# OMODRI_AbsEnc.net
KiCad netlist of a schematic drawn in Altium Designer
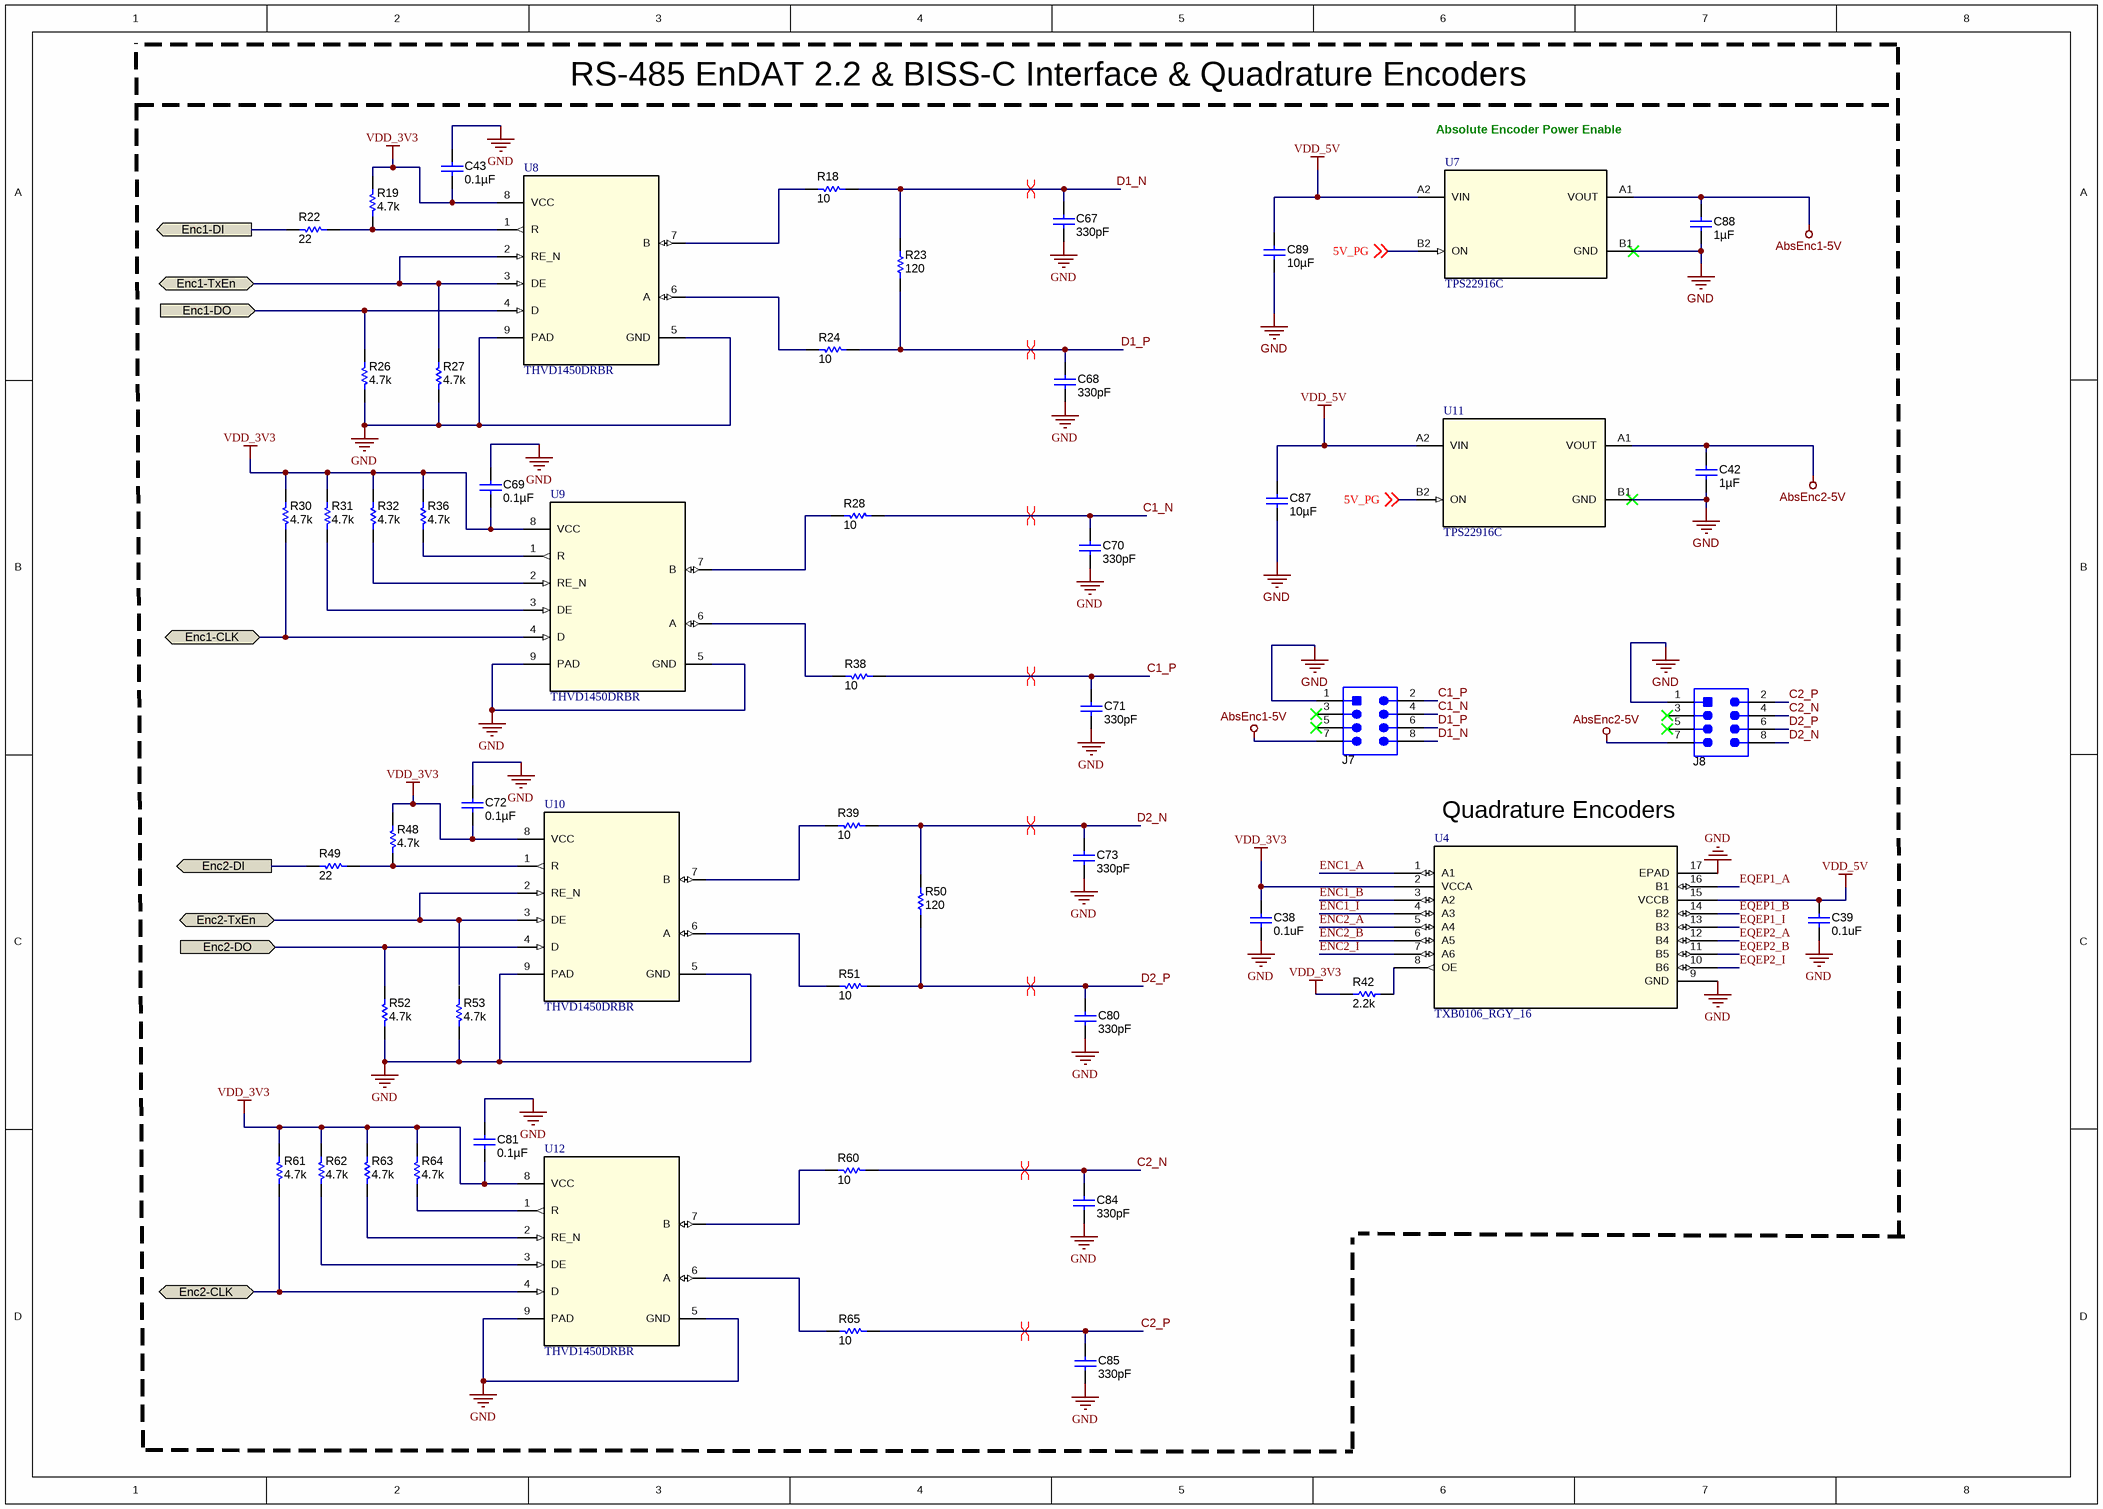
[diagram p0: OMODRI_AbsEnc.SchDoc]

(export (version "E")
  (design (tool "Eeschema 10.0.6"))
  (components
    (comp (ref "C38")
      (value "CL05B104KP5NNNC")
      (footprint "0402")
      (description "CAP, CERM, 0.1 uF, 10 V, +/- 10%, X7R, 0402")
      (fields
        (field (name "VALUEDISPLAYED") "0.1uF")
        (field (name "MANUFACTURER") "Samsung Electro-Mechanics")
        (field (name "PUBLISHER") "Texas Instruments")
      )
      (libsource (lib "Altium Vault - TI") (part "Capacitor"))
    )
    (comp (ref "C39")
      (value "CL05B104KP5NNNC")
      (footprint "0402")
      (description "CAP, CERM, 0.1 uF, 10 V, +/- 10%, X7R, 0402")
      (fields
        (field (name "VALUEDISPLAYED") "0.1uF")
        (field (name "MANUFACTURER") "Samsung Electro-Mechanics")
        (field (name "PUBLISHER") "Texas Instruments")
      )
      (libsource (lib "Altium Vault - TI") (part "Capacitor"))
    )
    (comp (ref "C42")
      (value "TMK212BJ105KG-T")
      (footprint "0805_HV")
      (description "CAP, CERM, 1 µF, 20 V, +/- 10%, X5R, 0805")
      (fields
        (field (name "VALUEDISPLAYED") "1µF")
        (field (name "MANUFACTURER") "Taiyo Yuden")
        (field (name "PUBLISHER") "Texas Instruments")
      )
      (libsource (lib "Capacitor_Ceramic") (part "TMK212BJ105KG-T"))
    )
    (comp (ref "C43")
      (value "06033D104KAT2A")
      (footprint "0603")
      (description "CAP, CERM, 0.1uF, 25V, +/-10%, X5R, 0603")
      (fields
        (field (name "VALUEDISPLAYED") "0.1µF")
        (field (name "MANUFACTURER") "AVX")
        (field (name "PUBLISHER") "Texas Instruments")
      )
      (libsource (lib "Capacitor_Ceramic") (part "06033D104KAT2A"))
    )
    (comp (ref "C67")
      (value "GRM188R71H331KA01D")
      (footprint "0603")
      (description "CAP, CERM, 330pF, 50V, +/-10%, X7R, 0603")
      (fields
        (field (name "VALUEDISPLAYED") "330pF")
        (field (name "MANUFACTURER") "MuRata")
        (field (name "PUBLISHER") "Texas Instruments")
      )
      (libsource (lib "Capacitor_Ceramic") (part "GRM188R71H331KA01D"))
    )
    (comp (ref "C68")
      (value "GRM188R71H331KA01D")
      (footprint "0603")
      (description "CAP, CERM, 330pF, 50V, +/-10%, X7R, 0603")
      (fields
        (field (name "VALUEDISPLAYED") "330pF")
        (field (name "MANUFACTURER") "MuRata")
        (field (name "PUBLISHER") "Texas Instruments")
      )
      (libsource (lib "Capacitor_Ceramic") (part "GRM188R71H331KA01D"))
    )
    (comp (ref "C69")
      (value "06033D104KAT2A")
      (footprint "0603")
      (description "CAP, CERM, 0.1uF, 25V, +/-10%, X5R, 0603")
      (fields
        (field (name "VALUEDISPLAYED") "0.1µF")
        (field (name "MANUFACTURER") "AVX")
        (field (name "PUBLISHER") "Texas Instruments")
      )
      (libsource (lib "Capacitor_Ceramic") (part "06033D104KAT2A"))
    )
    (comp (ref "C70")
      (value "GRM188R71H331KA01D")
      (footprint "0603")
      (description "CAP, CERM, 330pF, 50V, +/-10%, X7R, 0603")
      (fields
        (field (name "VALUEDISPLAYED") "330pF")
        (field (name "MANUFACTURER") "MuRata")
        (field (name "PUBLISHER") "Texas Instruments")
      )
      (libsource (lib "Capacitor_Ceramic") (part "GRM188R71H331KA01D"))
    )
    (comp (ref "C71")
      (value "GRM188R71H331KA01D")
      (footprint "0603")
      (description "CAP, CERM, 330pF, 50V, +/-10%, X7R, 0603")
      (fields
        (field (name "VALUEDISPLAYED") "330pF")
        (field (name "MANUFACTURER") "MuRata")
        (field (name "PUBLISHER") "Texas Instruments")
      )
      (libsource (lib "Capacitor_Ceramic") (part "GRM188R71H331KA01D"))
    )
    (comp (ref "C72")
      (value "06033D104KAT2A")
      (footprint "0603")
      (description "CAP, CERM, 0.1uF, 25V, +/-10%, X5R, 0603")
      (fields
        (field (name "VALUEDISPLAYED") "0.1µF")
        (field (name "MANUFACTURER") "AVX")
        (field (name "PUBLISHER") "Texas Instruments")
      )
      (libsource (lib "Capacitor_Ceramic") (part "06033D104KAT2A"))
    )
    (comp (ref "C73")
      (value "GRM188R71H331KA01D")
      (footprint "0603")
      (description "CAP, CERM, 330pF, 50V, +/-10%, X7R, 0603")
      (fields
        (field (name "VALUEDISPLAYED") "330pF")
        (field (name "MANUFACTURER") "MuRata")
        (field (name "PUBLISHER") "Texas Instruments")
      )
      (libsource (lib "Capacitor_Ceramic") (part "GRM188R71H331KA01D"))
    )
    (comp (ref "C80")
      (value "GRM188R71H331KA01D")
      (footprint "0603")
      (description "CAP, CERM, 330pF, 50V, +/-10%, X7R, 0603")
      (fields
        (field (name "VALUEDISPLAYED") "330pF")
        (field (name "MANUFACTURER") "MuRata")
        (field (name "PUBLISHER") "Texas Instruments")
      )
      (libsource (lib "Capacitor_Ceramic") (part "GRM188R71H331KA01D"))
    )
    (comp (ref "C81")
      (value "06033D104KAT2A")
      (footprint "0603")
      (description "CAP, CERM, 0.1uF, 25V, +/-10%, X5R, 0603")
      (fields
        (field (name "VALUEDISPLAYED") "0.1µF")
        (field (name "MANUFACTURER") "AVX")
        (field (name "PUBLISHER") "Texas Instruments")
      )
      (libsource (lib "Capacitor_Ceramic") (part "06033D104KAT2A"))
    )
    (comp (ref "C84")
      (value "GRM188R71H331KA01D")
      (footprint "0603")
      (description "CAP, CERM, 330pF, 50V, +/-10%, X7R, 0603")
      (fields
        (field (name "VALUEDISPLAYED") "330pF")
        (field (name "MANUFACTURER") "MuRata")
        (field (name "PUBLISHER") "Texas Instruments")
      )
      (libsource (lib "Capacitor_Ceramic") (part "GRM188R71H331KA01D"))
    )
    (comp (ref "C85")
      (value "GRM188R71H331KA01D")
      (footprint "0603")
      (description "CAP, CERM, 330pF, 50V, +/-10%, X7R, 0603")
      (fields
        (field (name "VALUEDISPLAYED") "330pF")
        (field (name "MANUFACTURER") "MuRata")
        (field (name "PUBLISHER") "Texas Instruments")
      )
      (libsource (lib "Capacitor_Ceramic") (part "GRM188R71H331KA01D"))
    )
    (comp (ref "C87")
      (value "GRM21BR61E106KA73L")
      (footprint "0805_HV")
      (description "CAP, CERM, 10 µF, 25 V,+/- 10%, X5R, 0805")
      (fields
        (field (name "VALUEDISPLAYED") "10µF")
        (field (name "MANUFACTURER") "MuRata")
        (field (name "PUBLISHER") "Texas Instruments")
      )
      (libsource (lib "Capacitor_Ceramic") (part "GRM21BR61E106KA73L"))
    )
    (comp (ref "C88")
      (value "TMK212BJ105KG-T")
      (footprint "0805_HV")
      (description "CAP, CERM, 1 µF, 20 V, +/- 10%, X5R, 0805")
      (fields
        (field (name "VALUEDISPLAYED") "1µF")
        (field (name "MANUFACTURER") "Taiyo Yuden")
        (field (name "PUBLISHER") "Texas Instruments")
      )
      (libsource (lib "Capacitor_Ceramic") (part "TMK212BJ105KG-T"))
    )
    (comp (ref "C89")
      (value "GRM21BR61E106KA73L")
      (footprint "0805_HV")
      (description "CAP, CERM, 10 µF, 25 V,+/- 10%, X5R, 0805")
      (fields
        (field (name "VALUEDISPLAYED") "10µF")
        (field (name "MANUFACTURER") "MuRata")
        (field (name "PUBLISHER") "Texas Instruments")
      )
      (libsource (lib "Capacitor_Ceramic") (part "GRM21BR61E106KA73L"))
    )
    (comp (ref "J7")
      (value "70246-0801")
      (footprint "Molex_70246-0801")
      (description "Header(shrouded), 2.54mm, 4x2, Gold, TH")
      (fields
        (field (name "MANUFACTURER") "Molex")
        (field (name "SYMBOLCREATOR") "a0411947")
        (field (name "PUBLISHER") "Texas Instruments")
      )
      (libsource (lib "Connectors_Molex") (part "70246-0801"))
    )
    (comp (ref "J8")
      (value "70246-0801")
      (footprint "Molex_70246-0801")
      (description "Header(shrouded), 2.54mm, 4x2, Gold, TH")
      (fields
        (field (name "MANUFACTURER") "Molex")
        (field (name "SYMBOLCREATOR") "a0411947")
        (field (name "PUBLISHER") "Texas Instruments")
      )
      (libsource (lib "Connectors_Molex") (part "70246-0801"))
    )
    (comp (ref "R18")
      (value "10")
      (footprint "0603")
      (description "RES, 10 ohm, 5%, 0.25W, 0603")
      (fields
        (field (name "PARTNUMBER") "CRCW060310R0JNEAHP")
        (field (name "MANUFACTURER") "Vishay-Dale")
        (field (name "PUBLISHER") "Texas Instruments")
      )
      (libsource (lib "Resistor_0603") (part "CRCW060310R0JNEAHP"))
    )
    (comp (ref "R19")
      (value "4.7k")
      (footprint "0603")
      (description "RES, 4.7k ohm, 5%, 0.1W, 0603")
      (fields
        (field (name "PARTNUMBER") "CRCW06034K70JNEA")
        (field (name "MANUFACTURER") "Vishay-Dale")
        (field (name "PUBLISHER") "Texas Instruments")
      )
      (libsource (lib "Resistor_0603") (part "CRCW06034K70JNEA"))
    )
    (comp (ref "R22")
      (value "22")
      (footprint "0603")
      (description "RES, 22 ohm, 5%, 0.1W, 0603")
      (fields
        (field (name "PARTNUMBER") "CRCW060322R0JNEA")
        (field (name "MANUFACTURER") "Vishay-Dale")
        (field (name "PUBLISHER") "Texas Instruments")
      )
      (libsource (lib "Resistor_0603") (part "CRCW060322R0JNEA"))
    )
    (comp (ref "R23")
      (value "CRCW0603120RJNEA")
      (footprint "0603")
      (description "RES, 120, 5%, 0.1 W, 0603")
      (fields
        (field (name "VALUEDISPLAYED") "120")
        (field (name "MANUFACTURER") "Vishay-Dale")
        (field (name "PUBLISHER") "Texas Instruments")
      )
      (libsource (lib "Resistor_0603") (part "CRCW0603120RJNEA"))
    )
    (comp (ref "R24")
      (value "10")
      (footprint "0603")
      (description "RES, 10 ohm, 5%, 0.25W, 0603")
      (fields
        (field (name "PARTNUMBER") "CRCW060310R0JNEAHP")
        (field (name "MANUFACTURER") "Vishay-Dale")
        (field (name "PUBLISHER") "Texas Instruments")
      )
      (libsource (lib "Resistor_0603") (part "CRCW060310R0JNEAHP"))
    )
    (comp (ref "R26")
      (value "4.7k")
      (footprint "0603")
      (description "RES, 4.7k ohm, 5%, 0.1W, 0603")
      (fields
        (field (name "PARTNUMBER") "CRCW06034K70JNEA")
        (field (name "MANUFACTURER") "Vishay-Dale")
        (field (name "PUBLISHER") "Texas Instruments")
      )
      (libsource (lib "Resistor_0603") (part "CRCW06034K70JNEA"))
    )
    (comp (ref "R27")
      (value "4.7k")
      (footprint "0603")
      (description "RES, 4.7k ohm, 5%, 0.1W, 0603")
      (fields
        (field (name "PARTNUMBER") "CRCW06034K70JNEA")
        (field (name "MANUFACTURER") "Vishay-Dale")
        (field (name "PUBLISHER") "Texas Instruments")
      )
      (libsource (lib "Resistor_0603") (part "CRCW06034K70JNEA"))
    )
    (comp (ref "R28")
      (value "10")
      (footprint "0603")
      (description "RES, 10 ohm, 5%, 0.25W, 0603")
      (fields
        (field (name "PARTNUMBER") "CRCW060310R0JNEAHP")
        (field (name "MANUFACTURER") "Vishay-Dale")
        (field (name "PUBLISHER") "Texas Instruments")
      )
      (libsource (lib "Resistor_0603") (part "CRCW060310R0JNEAHP"))
    )
    (comp (ref "R30")
      (value "4.7k")
      (footprint "0603")
      (description "RES, 4.7k ohm, 5%, 0.1W, 0603")
      (fields
        (field (name "PARTNUMBER") "CRCW06034K70JNEA")
        (field (name "MANUFACTURER") "Vishay-Dale")
        (field (name "PUBLISHER") "Texas Instruments")
      )
      (libsource (lib "Resistor_0603") (part "CRCW06034K70JNEA"))
    )
    (comp (ref "R31")
      (value "4.7k")
      (footprint "0603")
      (description "RES, 4.7k ohm, 5%, 0.1W, 0603")
      (fields
        (field (name "PARTNUMBER") "CRCW06034K70JNEA")
        (field (name "MANUFACTURER") "Vishay-Dale")
        (field (name "PUBLISHER") "Texas Instruments")
      )
      (libsource (lib "Resistor_0603") (part "CRCW06034K70JNEA"))
    )
    (comp (ref "R32")
      (value "4.7k")
      (footprint "0603")
      (description "RES, 4.7k ohm, 5%, 0.1W, 0603")
      (fields
        (field (name "PARTNUMBER") "CRCW06034K70JNEA")
        (field (name "MANUFACTURER") "Vishay-Dale")
        (field (name "PUBLISHER") "Texas Instruments")
      )
      (libsource (lib "Resistor_0603") (part "CRCW06034K70JNEA"))
    )
    (comp (ref "R36")
      (value "4.7k")
      (footprint "0603")
      (description "RES, 4.7k ohm, 5%, 0.1W, 0603")
      (fields
        (field (name "PARTNUMBER") "CRCW06034K70JNEA")
        (field (name "MANUFACTURER") "Vishay-Dale")
        (field (name "PUBLISHER") "Texas Instruments")
      )
      (libsource (lib "Resistor_0603") (part "CRCW06034K70JNEA"))
    )
    (comp (ref "R38")
      (value "10")
      (footprint "0603")
      (description "RES, 10 ohm, 5%, 0.25W, 0603")
      (fields
        (field (name "PARTNUMBER") "CRCW060310R0JNEAHP")
        (field (name "MANUFACTURER") "Vishay-Dale")
        (field (name "PUBLISHER") "Texas Instruments")
      )
      (libsource (lib "Resistor_0603") (part "CRCW060310R0JNEAHP"))
    )
    (comp (ref "R39")
      (value "10")
      (footprint "0603")
      (description "RES, 10 ohm, 5%, 0.25W, 0603")
      (fields
        (field (name "PARTNUMBER") "CRCW060310R0JNEAHP")
        (field (name "MANUFACTURER") "Vishay-Dale")
        (field (name "PUBLISHER") "Texas Instruments")
      )
      (libsource (lib "Resistor_0603") (part "CRCW060310R0JNEAHP"))
    )
    (comp (ref "R42")
      (value "CRCW02012K20JNED")
      (footprint "0201")
      (description "RES, 2.2 k, 5%, 0.05 W, 0201")
      (fields (field (name "MANUFACTURER") "Vishay-Dale") (field (name "VALUEDISPLAYED") "2.2k"))
      (libsource (lib "Altium Vault - TI") (part "Resistor"))
    )
    (comp (ref "R48")
      (value "4.7k")
      (footprint "0603")
      (description "RES, 4.7k ohm, 5%, 0.1W, 0603")
      (fields
        (field (name "PARTNUMBER") "CRCW06034K70JNEA")
        (field (name "MANUFACTURER") "Vishay-Dale")
        (field (name "PUBLISHER") "Texas Instruments")
      )
      (libsource (lib "Resistor_0603") (part "CRCW06034K70JNEA"))
    )
    (comp (ref "R49")
      (value "22")
      (footprint "0603")
      (description "RES, 22 ohm, 5%, 0.1W, 0603")
      (fields
        (field (name "PARTNUMBER") "CRCW060322R0JNEA")
        (field (name "MANUFACTURER") "Vishay-Dale")
        (field (name "PUBLISHER") "Texas Instruments")
      )
      (libsource (lib "Resistor_0603") (part "CRCW060322R0JNEA"))
    )
    (comp (ref "R50")
      (value "CRCW0603120RJNEA")
      (footprint "0603")
      (description "RES, 120, 5%, 0.1 W, 0603")
      (fields
        (field (name "VALUEDISPLAYED") "120")
        (field (name "MANUFACTURER") "Vishay-Dale")
        (field (name "PUBLISHER") "Texas Instruments")
      )
      (libsource (lib "Resistor_0603") (part "CRCW0603120RJNEA"))
    )
    (comp (ref "R51")
      (value "10")
      (footprint "0603")
      (description "RES, 10 ohm, 5%, 0.25W, 0603")
      (fields
        (field (name "PARTNUMBER") "CRCW060310R0JNEAHP")
        (field (name "MANUFACTURER") "Vishay-Dale")
        (field (name "PUBLISHER") "Texas Instruments")
      )
      (libsource (lib "Resistor_0603") (part "CRCW060310R0JNEAHP"))
    )
    (comp (ref "R52")
      (value "4.7k")
      (footprint "0603")
      (description "RES, 4.7k ohm, 5%, 0.1W, 0603")
      (fields
        (field (name "PARTNUMBER") "CRCW06034K70JNEA")
        (field (name "MANUFACTURER") "Vishay-Dale")
        (field (name "PUBLISHER") "Texas Instruments")
      )
      (libsource (lib "Resistor_0603") (part "CRCW06034K70JNEA"))
    )
    (comp (ref "R53")
      (value "4.7k")
      (footprint "0603")
      (description "RES, 4.7k ohm, 5%, 0.1W, 0603")
      (fields
        (field (name "PARTNUMBER") "CRCW06034K70JNEA")
        (field (name "MANUFACTURER") "Vishay-Dale")
        (field (name "PUBLISHER") "Texas Instruments")
      )
      (libsource (lib "Resistor_0603") (part "CRCW06034K70JNEA"))
    )
    (comp (ref "R60")
      (value "10")
      (footprint "0603")
      (description "RES, 10 ohm, 5%, 0.25W, 0603")
      (fields
        (field (name "PARTNUMBER") "CRCW060310R0JNEAHP")
        (field (name "MANUFACTURER") "Vishay-Dale")
        (field (name "PUBLISHER") "Texas Instruments")
      )
      (libsource (lib "Resistor_0603") (part "CRCW060310R0JNEAHP"))
    )
    (comp (ref "R61")
      (value "4.7k")
      (footprint "0603")
      (description "RES, 4.7k ohm, 5%, 0.1W, 0603")
      (fields
        (field (name "PARTNUMBER") "CRCW06034K70JNEA")
        (field (name "MANUFACTURER") "Vishay-Dale")
        (field (name "PUBLISHER") "Texas Instruments")
      )
      (libsource (lib "Resistor_0603") (part "CRCW06034K70JNEA"))
    )
    (comp (ref "R62")
      (value "4.7k")
      (footprint "0603")
      (description "RES, 4.7k ohm, 5%, 0.1W, 0603")
      (fields
        (field (name "PARTNUMBER") "CRCW06034K70JNEA")
        (field (name "MANUFACTURER") "Vishay-Dale")
        (field (name "PUBLISHER") "Texas Instruments")
      )
      (libsource (lib "Resistor_0603") (part "CRCW06034K70JNEA"))
    )
    (comp (ref "R63")
      (value "4.7k")
      (footprint "0603")
      (description "RES, 4.7k ohm, 5%, 0.1W, 0603")
      (fields
        (field (name "PARTNUMBER") "CRCW06034K70JNEA")
        (field (name "MANUFACTURER") "Vishay-Dale")
        (field (name "PUBLISHER") "Texas Instruments")
      )
      (libsource (lib "Resistor_0603") (part "CRCW06034K70JNEA"))
    )
    (comp (ref "R64")
      (value "4.7k")
      (footprint "0603")
      (description "RES, 4.7k ohm, 5%, 0.1W, 0603")
      (fields
        (field (name "PARTNUMBER") "CRCW06034K70JNEA")
        (field (name "MANUFACTURER") "Vishay-Dale")
        (field (name "PUBLISHER") "Texas Instruments")
      )
      (libsource (lib "Resistor_0603") (part "CRCW06034K70JNEA"))
    )
    (comp (ref "R65")
      (value "10")
      (footprint "0603")
      (description "RES, 10 ohm, 5%, 0.25W, 0603")
      (fields
        (field (name "PARTNUMBER") "CRCW060310R0JNEAHP")
        (field (name "MANUFACTURER") "Vishay-Dale")
        (field (name "PUBLISHER") "Texas Instruments")
      )
      (libsource (lib "Resistor_0603") (part "CRCW060310R0JNEAHP"))
    )
    (comp (ref "U4")
      (value "TXB0106_RGY_16")
      (footprint "RGY16_2P55X2P05")
      (fields
        (field (name "MANUFACTURER_PART_NUMBER") "txb0106_rgy_16")
        (field (name "GENERIC_PART_NUMBER") "TXB0106")
        (field (name "MANUFACTURER") "Texas Instruments")
      )
      (libsource (lib "Texas_Instruments") (part "TXB0106_RGY_16"))
    )
    (comp (ref "U7")
      (value "TPS22916C")
      (footprint "YFP0004ABAB")
      (description "TPS22916CY Single-Channel Ultra-Low Leakage Load Switch 2A 60 mO 1V to 5.5V 4-Pin DSBGA T/R")
      (fields
        (field (name "MANUFACTURER") "Texas Instruments")
        (field (name "MANUFACTURER PART NUMBER") "TPS22916CYFPR")
      )
      (libsource (lib "Texas_Instruments") (part "TPS22916C"))
    )
    (comp (ref "U8")
      (value "THVD1450DRBR")
      (footprint "DRB0008F")
      (fields (field (name "MANUFACTURER") "Texas Instruments"))
      (libsource (lib "Texas_Instruments") (part "THVD1450DRBR"))
    )
    (comp (ref "U9")
      (value "THVD1450DRBR")
      (footprint "DRB0008F")
      (fields (field (name "MANUFACTURER") "Texas Instruments"))
      (libsource (lib "Texas_Instruments") (part "THVD1450DRBR"))
    )
    (comp (ref "U10")
      (value "THVD1450DRBR")
      (footprint "DRB0008F")
      (fields (field (name "MANUFACTURER") "Texas Instruments"))
      (libsource (lib "Texas_Instruments") (part "THVD1450DRBR"))
    )
    (comp (ref "U11")
      (value "TPS22916C")
      (footprint "YFP0004ABAB")
      (description "TPS22916CY Single-Channel Ultra-Low Leakage Load Switch 2A 60 mO 1V to 5.5V 4-Pin DSBGA T/R")
      (fields
        (field (name "MANUFACTURER") "Texas Instruments")
        (field (name "MANUFACTURER PART NUMBER") "TPS22916CYFPR")
      )
      (libsource (lib "Texas_Instruments") (part "TPS22916C"))
    )
    (comp (ref "U12")
      (value "THVD1450DRBR")
      (footprint "DRB0008F")
      (fields (field (name "MANUFACTURER") "Texas Instruments"))
      (libsource (lib "Texas_Instruments") (part "THVD1450DRBR"))
    )
  )
  (nets
    (net (code "1") (name "/C1_N") (class "Default")
      (node (ref "C70") (pin "2") (pinfunction "2_2") (pintype "passive"))
      (node (ref "J7") (pin "4") (pinfunction "4_4") (pintype "passive"))
      (node (ref "R28") (pin "1") (pinfunction "1_1") (pintype "passive"))
    )
    (net (code "2") (name "/C1_P") (class "Default")
      (node (ref "C71") (pin "1") (pinfunction "1_1") (pintype "passive"))
      (node (ref "J7") (pin "2") (pinfunction "2_2") (pintype "passive"))
      (node (ref "R38") (pin "1") (pinfunction "1_1") (pintype "passive"))
    )
    (net (code "3") (name "/C2_N") (class "Default")
      (node (ref "C84") (pin "2") (pinfunction "2_2") (pintype "passive"))
      (node (ref "J8") (pin "4") (pinfunction "4_4") (pintype "passive"))
      (node (ref "R60") (pin "1") (pinfunction "1_1") (pintype "passive"))
    )
    (net (code "4") (name "/C2_P") (class "Default")
      (node (ref "C85") (pin "1") (pinfunction "1_1") (pintype "passive"))
      (node (ref "J8") (pin "2") (pinfunction "2_2") (pintype "passive"))
      (node (ref "R65") (pin "1") (pinfunction "1_1") (pintype "passive"))
    )
    (net (code "5") (name "/D1_N") (class "Default")
      (node (ref "C67") (pin "2") (pinfunction "2_2") (pintype "passive"))
      (node (ref "J7") (pin "8") (pinfunction "8_8") (pintype "passive"))
      (node (ref "R18") (pin "1") (pinfunction "1_1") (pintype "passive"))
      (node (ref "R23") (pin "2") (pinfunction "2_2") (pintype "passive"))
    )
    (net (code "6") (name "/D1_P") (class "Default")
      (node (ref "C68") (pin "1") (pinfunction "1_1") (pintype "passive"))
      (node (ref "J7") (pin "6") (pinfunction "6_6") (pintype "passive"))
      (node (ref "R23") (pin "1") (pinfunction "1_1") (pintype "passive"))
      (node (ref "R24") (pin "1") (pinfunction "1_1") (pintype "passive"))
    )
    (net (code "7") (name "/D2_N") (class "Default")
      (node (ref "C73") (pin "2") (pinfunction "2_2") (pintype "passive"))
      (node (ref "J8") (pin "8") (pinfunction "8_8") (pintype "passive"))
      (node (ref "R39") (pin "1") (pinfunction "1_1") (pintype "passive"))
      (node (ref "R50") (pin "2") (pinfunction "2_2") (pintype "passive"))
    )
    (net (code "8") (name "/D2_P") (class "Default")
      (node (ref "C80") (pin "1") (pinfunction "1_1") (pintype "passive"))
      (node (ref "J8") (pin "6") (pinfunction "6_6") (pintype "passive"))
      (node (ref "R50") (pin "1") (pinfunction "1_1") (pintype "passive"))
      (node (ref "R51") (pin "1") (pinfunction "1_1") (pintype "passive"))
    )
    (net (code "9") (name "/ENC1_A") (class "Default")
      (node (ref "U4") (pin "1") (pinfunction "A1_1") (pintype "bidirectional"))
    )
    (net (code "10") (name "/ENC1_B") (class "Default")
      (node (ref "U4") (pin "3") (pinfunction "A2_3") (pintype "bidirectional"))
    )
    (net (code "11") (name "/ENC1_I") (class "Default")
      (node (ref "U4") (pin "4") (pinfunction "A3_4") (pintype "bidirectional"))
    )
    (net (code "12") (name "/ENC2_A") (class "Default")
      (node (ref "U4") (pin "5") (pinfunction "A4_5") (pintype "bidirectional"))
    )
    (net (code "13") (name "/ENC2_B") (class "Default")
      (node (ref "U4") (pin "6") (pinfunction "A5_6") (pintype "bidirectional"))
    )
    (net (code "14") (name "/ENC2_I") (class "Default")
      (node (ref "U4") (pin "7") (pinfunction "A6_7") (pintype "bidirectional"))
    )
    (net (code "15") (name "/EQEP1_A") (class "Default")
      (node (ref "U4") (pin "16") (pinfunction "B1_16") (pintype "bidirectional"))
    )
    (net (code "16") (name "/EQEP1_B") (class "Default")
      (node (ref "U4") (pin "14") (pinfunction "B2_14") (pintype "bidirectional"))
    )
    (net (code "17") (name "/EQEP1_I") (class "Default")
      (node (ref "U4") (pin "13") (pinfunction "B3_13") (pintype "bidirectional"))
    )
    (net (code "18") (name "/EQEP2_A") (class "Default")
      (node (ref "U4") (pin "12") (pinfunction "B4_12") (pintype "bidirectional"))
    )
    (net (code "19") (name "/EQEP2_B") (class "Default")
      (node (ref "U4") (pin "11") (pinfunction "B5_11") (pintype "bidirectional"))
    )
    (net (code "20") (name "/EQEP2_I") (class "Default")
      (node (ref "U4") (pin "10") (pinfunction "B6_10") (pintype "bidirectional"))
    )
    (net (code "21") (name "/Enc1-CLK") (class "Default")
      (node (ref "R30") (pin "2") (pinfunction "2_2") (pintype "passive"))
      (node (ref "U9") (pin "4") (pinfunction "D_4") (pintype "input"))
    )
    (net (code "22") (name "/Enc1-DI") (class "Default")
      (node (ref "R22") (pin "2") (pinfunction "2_2") (pintype "passive"))
    )
    (net (code "23") (name "/Enc1-DO") (class "Default")
      (node (ref "R26") (pin "1") (pinfunction "1_1") (pintype "passive"))
      (node (ref "U8") (pin "4") (pinfunction "D_4") (pintype "input"))
    )
    (net (code "24") (name "/Enc1-TxEn") (class "Default")
      (node (ref "U8") (pin "2") (pinfunction "RE_N_2") (pintype "input"))
      (node (ref "U8") (pin "3") (pinfunction "DE_3") (pintype "input"))
    )
    (net (code "25") (name "/Enc2-CLK") (class "Default")
      (node (ref "R61") (pin "2") (pinfunction "2_2") (pintype "passive"))
      (node (ref "U12") (pin "4") (pinfunction "D_4") (pintype "input"))
    )
    (net (code "26") (name "/Enc2-DI") (class "Default")
      (node (ref "R49") (pin "2") (pinfunction "2_2") (pintype "passive"))
    )
    (net (code "27") (name "/Enc2-DO") (class "Default")
      (node (ref "R52") (pin "1") (pinfunction "1_1") (pintype "passive"))
      (node (ref "U10") (pin "4") (pinfunction "D_4") (pintype "input"))
    )
    (net (code "28") (name "/Enc2-TxEn") (class "Default")
      (node (ref "U10") (pin "2") (pinfunction "RE_N_2") (pintype "input"))
      (node (ref "U10") (pin "3") (pinfunction "DE_3") (pintype "input"))
    )
    (net (code "29") (name "5V_PG") (class "Default")
      (node (ref "U11") (pin "B2") (pinfunction "ON_B2") (pintype "input"))
      (node (ref "U7") (pin "B2") (pinfunction "ON_B2") (pintype "input"))
    )
    (net (code "30") (name "AbsEnc1-5V") (class "Default")
      (node (ref "C88") (pin "1") (pinfunction "1_1") (pintype "passive"))
      (node (ref "J7") (pin "7") (pinfunction "7_7") (pintype "passive"))
      (node (ref "U7") (pin "A1") (pinfunction "VOUT_A1") (pintype "power_in"))
    )
    (net (code "31") (name "AbsEnc2-5V") (class "Default")
      (node (ref "C42") (pin "1") (pinfunction "1_1") (pintype "passive"))
      (node (ref "J8") (pin "7") (pinfunction "7_7") (pintype "passive"))
      (node (ref "U11") (pin "A1") (pinfunction "VOUT_A1") (pintype "power_in"))
    )
    (net (code "32") (name "GND") (class "Default")
      (node (ref "C38") (pin "2") (pinfunction "2_2") (pintype "passive"))
      (node (ref "C39") (pin "2") (pinfunction "2_2") (pintype "passive"))
      (node (ref "C42") (pin "2") (pinfunction "2_2") (pintype "passive"))
      (node (ref "C43") (pin "2") (pinfunction "2_2") (pintype "passive"))
      (node (ref "C67") (pin "1") (pinfunction "1_1") (pintype "passive"))
      (node (ref "C68") (pin "2") (pinfunction "2_2") (pintype "passive"))
      (node (ref "C69") (pin "2") (pinfunction "2_2") (pintype "passive"))
      (node (ref "C70") (pin "1") (pinfunction "1_1") (pintype "passive"))
      (node (ref "C71") (pin "2") (pinfunction "2_2") (pintype "passive"))
      (node (ref "C72") (pin "2") (pinfunction "2_2") (pintype "passive"))
      (node (ref "C73") (pin "1") (pinfunction "1_1") (pintype "passive"))
      (node (ref "C80") (pin "2") (pinfunction "2_2") (pintype "passive"))
      (node (ref "C81") (pin "2") (pinfunction "2_2") (pintype "passive"))
      (node (ref "C84") (pin "1") (pinfunction "1_1") (pintype "passive"))
      (node (ref "C85") (pin "2") (pinfunction "2_2") (pintype "passive"))
      (node (ref "C87") (pin "2") (pinfunction "2_2") (pintype "passive"))
      (node (ref "C88") (pin "2") (pinfunction "2_2") (pintype "passive"))
      (node (ref "C89") (pin "2") (pinfunction "2_2") (pintype "passive"))
      (node (ref "J7") (pin "1") (pinfunction "1_1") (pintype "passive"))
      (node (ref "J8") (pin "1") (pinfunction "1_1") (pintype "passive"))
      (node (ref "R26") (pin "2") (pinfunction "2_2") (pintype "passive"))
      (node (ref "R27") (pin "2") (pinfunction "2_2") (pintype "passive"))
      (node (ref "R52") (pin "2") (pinfunction "2_2") (pintype "passive"))
      (node (ref "R53") (pin "2") (pinfunction "2_2") (pintype "passive"))
      (node (ref "U10") (pin "5") (pinfunction "GND_5") (pintype "power_in"))
      (node (ref "U10") (pin "9") (pinfunction "PAD_9") (pintype "passive"))
      (node (ref "U11") (pin "B1") (pinfunction "GND_B1") (pintype "power_in"))
      (node (ref "U12") (pin "5") (pinfunction "GND_5") (pintype "power_in"))
      (node (ref "U12") (pin "9") (pinfunction "PAD_9") (pintype "passive"))
      (node (ref "U4") (pin "17") (pinfunction "EPAD_17") (pintype "passive"))
      (node (ref "U4") (pin "9") (pinfunction "GND_9") (pintype "power_in"))
      (node (ref "U7") (pin "B1") (pinfunction "GND_B1") (pintype "power_in"))
      (node (ref "U8") (pin "5") (pinfunction "GND_5") (pintype "power_in"))
      (node (ref "U8") (pin "9") (pinfunction "PAD_9") (pintype "passive"))
      (node (ref "U9") (pin "5") (pinfunction "GND_5") (pintype "power_in"))
      (node (ref "U9") (pin "9") (pinfunction "PAD_9") (pintype "passive"))
    )
    (net (code "33") (name "Net-(U4-OE)") (class "Default")
      (node (ref "R42") (pin "2") (pinfunction "2_2") (pintype "passive"))
      (node (ref "U4") (pin "8") (pinfunction "OE_8") (pintype "output"))
    )
    (net (code "34") (name "Net-(U8-A)") (class "Default")
      (node (ref "R24") (pin "2") (pinfunction "2_2") (pintype "passive"))
      (node (ref "U8") (pin "6") (pinfunction "A_6") (pintype "bidirectional"))
    )
    (net (code "35") (name "Net-(U8-B)") (class "Default")
      (node (ref "R18") (pin "2") (pinfunction "2_2") (pintype "passive"))
      (node (ref "U8") (pin "7") (pinfunction "B_7") (pintype "bidirectional"))
    )
    (net (code "36") (name "Net-(U8-R)") (class "Default")
      (node (ref "R19") (pin "1") (pinfunction "1_1") (pintype "passive"))
      (node (ref "R22") (pin "1") (pinfunction "1_1") (pintype "passive"))
      (node (ref "U8") (pin "1") (pinfunction "R_1") (pintype "output"))
    )
    (net (code "37") (name "Net-(U9-A)") (class "Default")
      (node (ref "R38") (pin "2") (pinfunction "2_2") (pintype "passive"))
      (node (ref "U9") (pin "6") (pinfunction "A_6") (pintype "bidirectional"))
    )
    (net (code "38") (name "Net-(U9-B)") (class "Default")
      (node (ref "R28") (pin "2") (pinfunction "2_2") (pintype "passive"))
      (node (ref "U9") (pin "7") (pinfunction "B_7") (pintype "bidirectional"))
    )
    (net (code "39") (name "Net-(U9-DE)") (class "Default")
      (node (ref "R31") (pin "2") (pinfunction "2_2") (pintype "passive"))
      (node (ref "U9") (pin "3") (pinfunction "DE_3") (pintype "input"))
    )
    (net (code "40") (name "Net-(U9-R)") (class "Default")
      (node (ref "R36") (pin "2") (pinfunction "2_2") (pintype "passive"))
      (node (ref "U9") (pin "1") (pinfunction "R_1") (pintype "output"))
    )
    (net (code "41") (name "Net-(U9-RE_N)") (class "Default")
      (node (ref "R32") (pin "2") (pinfunction "2_2") (pintype "passive"))
      (node (ref "U9") (pin "2") (pinfunction "RE_N_2") (pintype "input"))
    )
    (net (code "42") (name "Net-(U10-A)") (class "Default")
      (node (ref "R51") (pin "2") (pinfunction "2_2") (pintype "passive"))
      (node (ref "U10") (pin "6") (pinfunction "A_6") (pintype "bidirectional"))
    )
    (net (code "43") (name "Net-(U10-B)") (class "Default")
      (node (ref "R39") (pin "2") (pinfunction "2_2") (pintype "passive"))
      (node (ref "U10") (pin "7") (pinfunction "B_7") (pintype "bidirectional"))
    )
    (net (code "44") (name "Net-(U10-R)") (class "Default")
      (node (ref "R48") (pin "1") (pinfunction "1_1") (pintype "passive"))
      (node (ref "R49") (pin "1") (pinfunction "1_1") (pintype "passive"))
      (node (ref "U10") (pin "1") (pinfunction "R_1") (pintype "output"))
    )
    (net (code "45") (name "Net-(U12-A)") (class "Default")
      (node (ref "R65") (pin "2") (pinfunction "2_2") (pintype "passive"))
      (node (ref "U12") (pin "6") (pinfunction "A_6") (pintype "bidirectional"))
    )
    (net (code "46") (name "Net-(U12-B)") (class "Default")
      (node (ref "R60") (pin "2") (pinfunction "2_2") (pintype "passive"))
      (node (ref "U12") (pin "7") (pinfunction "B_7") (pintype "bidirectional"))
    )
    (net (code "47") (name "Net-(U12-DE)") (class "Default")
      (node (ref "R62") (pin "2") (pinfunction "2_2") (pintype "passive"))
      (node (ref "U12") (pin "3") (pinfunction "DE_3") (pintype "input"))
    )
    (net (code "48") (name "Net-(U12-R)") (class "Default")
      (node (ref "R64") (pin "2") (pinfunction "2_2") (pintype "passive"))
      (node (ref "U12") (pin "1") (pinfunction "R_1") (pintype "output"))
    )
    (net (code "49") (name "Net-(U12-RE_N)") (class "Default")
      (node (ref "R63") (pin "2") (pinfunction "2_2") (pintype "passive"))
      (node (ref "U12") (pin "2") (pinfunction "RE_N_2") (pintype "input"))
    )
    (net (code "50") (name "VDD_3V3") (class "Default")
      (node (ref "C38") (pin "1") (pinfunction "1_1") (pintype "passive"))
      (node (ref "C43") (pin "1") (pinfunction "1_1") (pintype "passive"))
      (node (ref "C69") (pin "1") (pinfunction "1_1") (pintype "passive"))
      (node (ref "C72") (pin "1") (pinfunction "1_1") (pintype "passive"))
      (node (ref "C81") (pin "1") (pinfunction "1_1") (pintype "passive"))
      (node (ref "R19") (pin "2") (pinfunction "2_2") (pintype "passive"))
      (node (ref "R30") (pin "1") (pinfunction "1_1") (pintype "passive"))
      (node (ref "R31") (pin "1") (pinfunction "1_1") (pintype "passive"))
      (node (ref "R32") (pin "1") (pinfunction "1_1") (pintype "passive"))
      (node (ref "R36") (pin "1") (pinfunction "1_1") (pintype "passive"))
      (node (ref "R42") (pin "1") (pinfunction "1_1") (pintype "passive"))
      (node (ref "R48") (pin "2") (pinfunction "2_2") (pintype "passive"))
      (node (ref "R61") (pin "1") (pinfunction "1_1") (pintype "passive"))
      (node (ref "R62") (pin "1") (pinfunction "1_1") (pintype "passive"))
      (node (ref "R63") (pin "1") (pinfunction "1_1") (pintype "passive"))
      (node (ref "R64") (pin "1") (pinfunction "1_1") (pintype "passive"))
      (node (ref "U10") (pin "8") (pinfunction "VCC_8") (pintype "power_in"))
      (node (ref "U12") (pin "8") (pinfunction "VCC_8") (pintype "power_in"))
      (node (ref "U4") (pin "2") (pinfunction "VCCA_2") (pintype "power_in"))
      (node (ref "U8") (pin "8") (pinfunction "VCC_8") (pintype "power_in"))
      (node (ref "U9") (pin "8") (pinfunction "VCC_8") (pintype "power_in"))
    )
    (net (code "51") (name "VDD_5V") (class "Default")
      (node (ref "C39") (pin "1") (pinfunction "1_1") (pintype "passive"))
      (node (ref "C87") (pin "1") (pinfunction "1_1") (pintype "passive"))
      (node (ref "C89") (pin "1") (pinfunction "1_1") (pintype "passive"))
      (node (ref "U11") (pin "A2") (pinfunction "VIN_A2") (pintype "power_in"))
      (node (ref "U4") (pin "15") (pinfunction "VCCB_15") (pintype "power_in"))
      (node (ref "U7") (pin "A2") (pinfunction "VIN_A2") (pintype "power_in"))
    )
    (net (code "52") (name "unconnected-(J7-Pad3)") (class "Default")
      (node (ref "J7") (pin "3") (pinfunction "3_3") (pintype "passive+no_connect"))
    )
    (net (code "53") (name "unconnected-(J7-Pad5)") (class "Default")
      (node (ref "J7") (pin "5") (pinfunction "5_5") (pintype "passive+no_connect"))
    )
    (net (code "54") (name "unconnected-(J8-Pad3)") (class "Default")
      (node (ref "J8") (pin "3") (pinfunction "3_3") (pintype "passive+no_connect"))
    )
    (net (code "55") (name "unconnected-(J8-Pad5)") (class "Default")
      (node (ref "J8") (pin "5") (pinfunction "5_5") (pintype "passive+no_connect"))
    )
    (net (code "56") (name "unconnected-(R27-Pad1)") (class "Default")
      (node (ref "R27") (pin "1") (pinfunction "1_1") (pintype "passive"))
    )
    (net (code "57") (name "unconnected-(R53-Pad1)") (class "Default")
      (node (ref "R53") (pin "1") (pinfunction "1_1") (pintype "passive"))
    )
  )
)
